# board.net
KiCad netlist of a schematic drawn in EAGLE
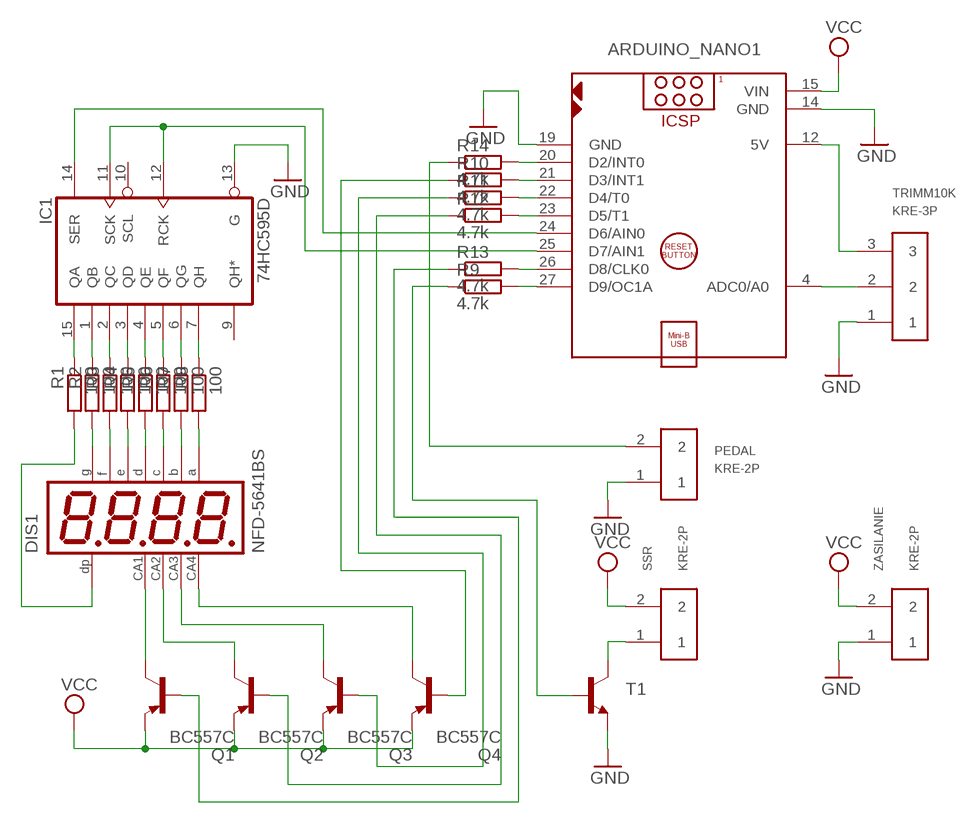
[diagram p0: schematic, sheet 1]

(export (version "E")
  (design (tool "Eeschema 10.0.6"))
  (components
    (comp (ref "ARDUINO_NANO1")
      (value "ARDUINO_NANO")
      (footprint "eagle-import:ARDUINO_NANO")
      (libsource (lib "eagle-import") (part "ARDUINO_NANO"))
    )
    (comp (ref "DIS1")
      (value "NFD-5641BS")
      (footprint "eagle-import:NFD-5641")
      (libsource (lib "eagle-import") (part "NFD-5641BS"))
    )
    (comp (ref "IC1")
      (value "74HC595D")
      (footprint "eagle-import:SO16")
      (libsource (lib "eagle-import") (part "74595DHC"))
    )
    (comp (ref "PEDAL")
      (value "KRE-2P")
      (footprint "eagle-import:KRE-2P")
      (libsource (lib "eagle-import") (part "KRE-2P"))
    )
    (comp (ref "Q1")
      (value "BC557C")
      (footprint "eagle-import:TO92-EBC")
      (libsource (lib "eagle-import") (part "BC557C"))
    )
    (comp (ref "Q2")
      (value "BC557C")
      (footprint "eagle-import:TO92-EBC")
      (libsource (lib "eagle-import") (part "BC557C"))
    )
    (comp (ref "Q3")
      (value "BC557C")
      (footprint "eagle-import:TO92-EBC")
      (libsource (lib "eagle-import") (part "BC557C"))
    )
    (comp (ref "Q4")
      (value "BC557C")
      (footprint "eagle-import:TO92-EBC")
      (libsource (lib "eagle-import") (part "BC557C"))
    )
    (comp (ref "R1")
      (value "100")
      (footprint "eagle-import:0207_10")
      (libsource (lib "eagle-import") (part "R-EU_0207/10"))
    )
    (comp (ref "R2")
      (value "100")
      (footprint "eagle-import:0207_10")
      (libsource (lib "eagle-import") (part "R-EU_0207/10"))
    )
    (comp (ref "R3")
      (value "100")
      (footprint "eagle-import:0207_10")
      (libsource (lib "eagle-import") (part "R-EU_0207/10"))
    )
    (comp (ref "R4")
      (value "100")
      (footprint "eagle-import:0207_10")
      (libsource (lib "eagle-import") (part "R-EU_0207/10"))
    )
    (comp (ref "R5")
      (value "100")
      (footprint "eagle-import:0207_10")
      (libsource (lib "eagle-import") (part "R-EU_0207/10"))
    )
    (comp (ref "R6")
      (value "100")
      (footprint "eagle-import:0207_10")
      (libsource (lib "eagle-import") (part "R-EU_0207/10"))
    )
    (comp (ref "R7")
      (value "100")
      (footprint "eagle-import:0207_10")
      (libsource (lib "eagle-import") (part "R-EU_0207/10"))
    )
    (comp (ref "R8")
      (value "100")
      (footprint "eagle-import:0207_10")
      (libsource (lib "eagle-import") (part "R-EU_0207/10"))
    )
    (comp (ref "R9")
      (value "4.7k")
      (footprint "eagle-import:0207_10")
      (libsource (lib "eagle-import") (part "R-EU_0207/10"))
    )
    (comp (ref "R10")
      (value "4.7k")
      (footprint "eagle-import:0207_10")
      (libsource (lib "eagle-import") (part "R-EU_0207/10"))
    )
    (comp (ref "R11")
      (value "4.7k")
      (footprint "eagle-import:0207_10")
      (libsource (lib "eagle-import") (part "R-EU_0207/10"))
    )
    (comp (ref "R12")
      (value "4.7k")
      (footprint "eagle-import:0207_10")
      (libsource (lib "eagle-import") (part "R-EU_0207/10"))
    )
    (comp (ref "R13")
      (value "4.7k")
      (footprint "eagle-import:0207_10")
      (libsource (lib "eagle-import") (part "R-EU_0207/10"))
    )
    (comp (ref "R14")
      (value "4.7k")
      (footprint "eagle-import:0207_10")
      (libsource (lib "eagle-import") (part "R-EU_0207/10"))
    )
    (comp (ref "SSR")
      (value "KRE-2P")
      (footprint "eagle-import:KRE-2P")
      (libsource (lib "eagle-import") (part "KRE-2P"))
    )
    (comp (ref "T1")
      (value "BC337-NPN-TO92-CBE")
      (footprint "eagle-import:TO92-CBE")
      (libsource (lib "eagle-import") (part "-NPN-TO92-CBEBC337"))
    )
    (comp (ref "TRIMM10K")
      (value "KRE-3P")
      (footprint "eagle-import:KRE-3P")
      (libsource (lib "eagle-import") (part "KRE-3P"))
    )
    (comp (ref "ZASILANIE")
      (value "KRE-2P")
      (footprint "eagle-import:KRE-2P")
      (libsource (lib "eagle-import") (part "KRE-2P"))
    )
  )
  (nets
    (net (code "1") (name "GND") (class "Default")
      (node (ref "ARDUINO_NANO1") (pin "14") (pinfunction "GND_14") (pintype "power_in"))
      (node (ref "ARDUINO_NANO1") (pin "19") (pinfunction "GND_19") (pintype "power_in"))
      (node (ref "IC1") (pin "13") (pinfunction "G_13") (pintype "input"))
      (node (ref "PEDAL") (pin "1") (pinfunction "1_1") (pintype "bidirectional"))
      (node (ref "T1") (pin "E") (pinfunction "E_E") (pintype "passive"))
      (node (ref "TRIMM10K") (pin "1") (pinfunction "1_1") (pintype "bidirectional"))
      (node (ref "ZASILANIE") (pin "1") (pinfunction "1_1") (pintype "bidirectional"))
    )
    (net (code "2") (name "Net-(ARDUINO_NANO1-5V)") (class "Default")
      (node (ref "ARDUINO_NANO1") (pin "12") (pinfunction "5V_12") (pintype "power_in"))
      (node (ref "TRIMM10K") (pin "3") (pinfunction "3_3") (pintype "bidirectional"))
    )
    (net (code "3") (name "Net-(ARDUINO_NANO1-ADC0{slash}A0)") (class "Default")
      (node (ref "ARDUINO_NANO1") (pin "4") (pinfunction "ADC0/A0_4") (pintype "bidirectional"))
      (node (ref "TRIMM10K") (pin "2") (pinfunction "2_2") (pintype "bidirectional"))
    )
    (net (code "4") (name "Net-(ARDUINO_NANO1-D2{slash}INT0)") (class "Default")
      (node (ref "ARDUINO_NANO1") (pin "20") (pinfunction "D2/INT0_20") (pintype "bidirectional"))
      (node (ref "R14") (pin "2") (pinfunction "2_2") (pintype "passive"))
    )
    (net (code "5") (name "Net-(ARDUINO_NANO1-D3{slash}INT1)") (class "Default")
      (node (ref "ARDUINO_NANO1") (pin "21") (pinfunction "D3/INT1_21") (pintype "bidirectional"))
      (node (ref "R10") (pin "2") (pinfunction "2_2") (pintype "passive"))
    )
    (net (code "6") (name "Net-(ARDUINO_NANO1-D4{slash}T0)") (class "Default")
      (node (ref "ARDUINO_NANO1") (pin "22") (pinfunction "D4/T0_22") (pintype "bidirectional"))
      (node (ref "R11") (pin "2") (pinfunction "2_2") (pintype "passive"))
    )
    (net (code "7") (name "Net-(ARDUINO_NANO1-D5{slash}T1)") (class "Default")
      (node (ref "ARDUINO_NANO1") (pin "23") (pinfunction "D5/T1_23") (pintype "bidirectional"))
      (node (ref "R12") (pin "2") (pinfunction "2_2") (pintype "passive"))
    )
    (net (code "8") (name "Net-(ARDUINO_NANO1-D6{slash}AIN0)") (class "Default")
      (node (ref "ARDUINO_NANO1") (pin "24") (pinfunction "D6/AIN0_24") (pintype "bidirectional"))
      (node (ref "IC1") (pin "14") (pinfunction "SER_14") (pintype "input"))
    )
    (net (code "9") (name "Net-(ARDUINO_NANO1-D7{slash}AIN1)") (class "Default")
      (node (ref "ARDUINO_NANO1") (pin "25") (pinfunction "D7/AIN1_25") (pintype "bidirectional"))
      (node (ref "IC1") (pin "11") (pinfunction "SCK_11") (pintype "input"))
      (node (ref "IC1") (pin "12") (pinfunction "RCK_12") (pintype "input"))
    )
    (net (code "10") (name "Net-(ARDUINO_NANO1-D8{slash}CLK0)") (class "Default")
      (node (ref "ARDUINO_NANO1") (pin "26") (pinfunction "D8/CLK0_26") (pintype "bidirectional"))
      (node (ref "R13") (pin "2") (pinfunction "2_2") (pintype "passive"))
    )
    (net (code "11") (name "Net-(ARDUINO_NANO1-D9{slash}OC1A)") (class "Default")
      (node (ref "ARDUINO_NANO1") (pin "27") (pinfunction "D9/OC1A_27") (pintype "bidirectional"))
      (node (ref "R9") (pin "2") (pinfunction "2_2") (pintype "passive"))
    )
    (net (code "12") (name "Net-(DIS1-PadP$1)") (class "Default")
      (node (ref "DIS1") (pin "P$1") (pinfunction "P$1_P$1") (pintype "bidirectional"))
      (node (ref "R4") (pin "2") (pinfunction "2_2") (pintype "passive"))
    )
    (net (code "13") (name "Net-(DIS1-PadP$2)") (class "Default")
      (node (ref "DIS1") (pin "P$2") (pinfunction "P$2_P$2") (pintype "bidirectional"))
      (node (ref "R5") (pin "2") (pinfunction "2_2") (pintype "passive"))
    )
    (net (code "14") (name "Net-(DIS1-PadP$3)") (class "Default")
      (node (ref "DIS1") (pin "P$3") (pinfunction "P$3_P$3") (pintype "bidirectional"))
      (node (ref "R1") (pin "2") (pinfunction "2_2") (pintype "passive"))
    )
    (net (code "15") (name "Net-(DIS1-PadP$4)") (class "Default")
      (node (ref "DIS1") (pin "P$4") (pinfunction "P$4_P$4") (pintype "bidirectional"))
      (node (ref "R6") (pin "2") (pinfunction "2_2") (pintype "passive"))
    )
    (net (code "16") (name "Net-(DIS1-PadP$5)") (class "Default")
      (node (ref "DIS1") (pin "P$5") (pinfunction "P$5_P$5") (pintype "bidirectional"))
      (node (ref "R2") (pin "2") (pinfunction "2_2") (pintype "passive"))
    )
    (net (code "17") (name "Net-(DIS1-PadP$6)") (class "Default")
      (node (ref "DIS1") (pin "P$6") (pinfunction "P$6_P$6") (pintype "bidirectional"))
      (node (ref "Q4") (pin "C") (pinfunction "C_C") (pintype "passive"))
    )
    (net (code "18") (name "Net-(DIS1-PadP$7)") (class "Default")
      (node (ref "DIS1") (pin "P$7") (pinfunction "P$7_P$7") (pintype "bidirectional"))
      (node (ref "R7") (pin "2") (pinfunction "2_2") (pintype "passive"))
    )
    (net (code "19") (name "Net-(DIS1-PadP$8)") (class "Default")
      (node (ref "DIS1") (pin "P$8") (pinfunction "P$8_P$8") (pintype "bidirectional"))
      (node (ref "Q3") (pin "C") (pinfunction "C_C") (pintype "passive"))
    )
    (net (code "20") (name "Net-(DIS1-PadP$9)") (class "Default")
      (node (ref "DIS1") (pin "P$9") (pinfunction "P$9_P$9") (pintype "bidirectional"))
      (node (ref "Q2") (pin "C") (pinfunction "C_C") (pintype "passive"))
    )
    (net (code "21") (name "Net-(DIS1-PadP$10)") (class "Default")
      (node (ref "DIS1") (pin "P$10") (pinfunction "P$10_P$10") (pintype "bidirectional"))
      (node (ref "R3") (pin "2") (pinfunction "2_2") (pintype "passive"))
    )
    (net (code "22") (name "Net-(DIS1-PadP$11)") (class "Default")
      (node (ref "DIS1") (pin "P$11") (pinfunction "P$11_P$11") (pintype "bidirectional"))
      (node (ref "R8") (pin "2") (pinfunction "2_2") (pintype "passive"))
    )
    (net (code "23") (name "Net-(DIS1-PadP$12)") (class "Default")
      (node (ref "DIS1") (pin "P$12") (pinfunction "P$12_P$12") (pintype "bidirectional"))
      (node (ref "Q1") (pin "C") (pinfunction "C_C") (pintype "passive"))
    )
    (net (code "24") (name "Net-(IC1A-QA)") (class "Default")
      (node (ref "IC1") (pin "15") (pinfunction "QA_15") (pintype "tri_state"))
      (node (ref "R1") (pin "1") (pinfunction "1_1") (pintype "passive"))
    )
    (net (code "25") (name "Net-(IC1A-QB)") (class "Default")
      (node (ref "IC1") (pin "1") (pinfunction "QB_1") (pintype "tri_state"))
      (node (ref "R2") (pin "1") (pinfunction "1_1") (pintype "passive"))
    )
    (net (code "26") (name "Net-(IC1A-QC)") (class "Default")
      (node (ref "IC1") (pin "2") (pinfunction "QC_2") (pintype "tri_state"))
      (node (ref "R3") (pin "1") (pinfunction "1_1") (pintype "passive"))
    )
    (net (code "27") (name "Net-(IC1A-QD)") (class "Default")
      (node (ref "IC1") (pin "3") (pinfunction "QD_3") (pintype "tri_state"))
      (node (ref "R4") (pin "1") (pinfunction "1_1") (pintype "passive"))
    )
    (net (code "28") (name "Net-(IC1A-QE)") (class "Default")
      (node (ref "IC1") (pin "4") (pinfunction "QE_4") (pintype "tri_state"))
      (node (ref "R5") (pin "1") (pinfunction "1_1") (pintype "passive"))
    )
    (net (code "29") (name "Net-(IC1A-QF)") (class "Default")
      (node (ref "IC1") (pin "5") (pinfunction "QF_5") (pintype "tri_state"))
      (node (ref "R6") (pin "1") (pinfunction "1_1") (pintype "passive"))
    )
    (net (code "30") (name "Net-(IC1A-QG)") (class "Default")
      (node (ref "IC1") (pin "6") (pinfunction "QG_6") (pintype "tri_state"))
      (node (ref "R7") (pin "1") (pinfunction "1_1") (pintype "passive"))
    )
    (net (code "31") (name "Net-(IC1A-QH)") (class "Default")
      (node (ref "IC1") (pin "7") (pinfunction "QH_7") (pintype "tri_state"))
      (node (ref "R8") (pin "1") (pinfunction "1_1") (pintype "passive"))
    )
    (net (code "32") (name "Net-(PEDAL-Pad2)") (class "Default")
      (node (ref "PEDAL") (pin "2") (pinfunction "2_2") (pintype "bidirectional"))
      (node (ref "R14") (pin "1") (pinfunction "1_1") (pintype "passive"))
    )
    (net (code "33") (name "Net-(Q1-PadB)") (class "Default")
      (node (ref "Q1") (pin "B") (pinfunction "B_B") (pintype "passive"))
      (node (ref "R13") (pin "1") (pinfunction "1_1") (pintype "passive"))
    )
    (net (code "34") (name "Net-(Q2-PadB)") (class "Default")
      (node (ref "Q2") (pin "B") (pinfunction "B_B") (pintype "passive"))
      (node (ref "R12") (pin "1") (pinfunction "1_1") (pintype "passive"))
    )
    (net (code "35") (name "Net-(Q3-PadB)") (class "Default")
      (node (ref "Q3") (pin "B") (pinfunction "B_B") (pintype "passive"))
      (node (ref "R11") (pin "1") (pinfunction "1_1") (pintype "passive"))
    )
    (net (code "36") (name "Net-(Q4-PadB)") (class "Default")
      (node (ref "Q4") (pin "B") (pinfunction "B_B") (pintype "passive"))
      (node (ref "R10") (pin "1") (pinfunction "1_1") (pintype "passive"))
    )
    (net (code "37") (name "Net-(R9-Pad1)") (class "Default")
      (node (ref "R9") (pin "1") (pinfunction "1_1") (pintype "passive"))
      (node (ref "T1") (pin "B") (pinfunction "B_B") (pintype "passive"))
    )
    (net (code "38") (name "Net-(SSR-Pad1)") (class "Default")
      (node (ref "SSR") (pin "1") (pinfunction "1_1") (pintype "bidirectional"))
      (node (ref "T1") (pin "C") (pinfunction "C_C") (pintype "passive"))
    )
    (net (code "39") (name "VCC") (class "Default")
      (node (ref "ARDUINO_NANO1") (pin "15") (pinfunction "VIN_15") (pintype "power_in"))
      (node (ref "Q1") (pin "E") (pinfunction "E_E") (pintype "passive"))
      (node (ref "Q2") (pin "E") (pinfunction "E_E") (pintype "passive"))
      (node (ref "Q3") (pin "E") (pinfunction "E_E") (pintype "passive"))
      (node (ref "Q4") (pin "E") (pinfunction "E_E") (pintype "passive"))
      (node (ref "SSR") (pin "2") (pinfunction "2_2") (pintype "bidirectional"))
      (node (ref "ZASILANIE") (pin "2") (pinfunction "2_2") (pintype "bidirectional"))
    )
    (net (code "40") (name "unconnected-(IC1A-QH*-Pad9)") (class "Default")
      (node (ref "IC1") (pin "9") (pinfunction "QH*_9") (pintype "tri_state"))
    )
    (net (code "41") (name "unconnected-(IC1A-SCL-Pad10)") (class "Default")
      (node (ref "IC1") (pin "10") (pinfunction "SCL_10") (pintype "input"))
    )
  )
)
